# ESP32_with_USBC.net
KiCad netlist of a schematic drawn in Altium Designer
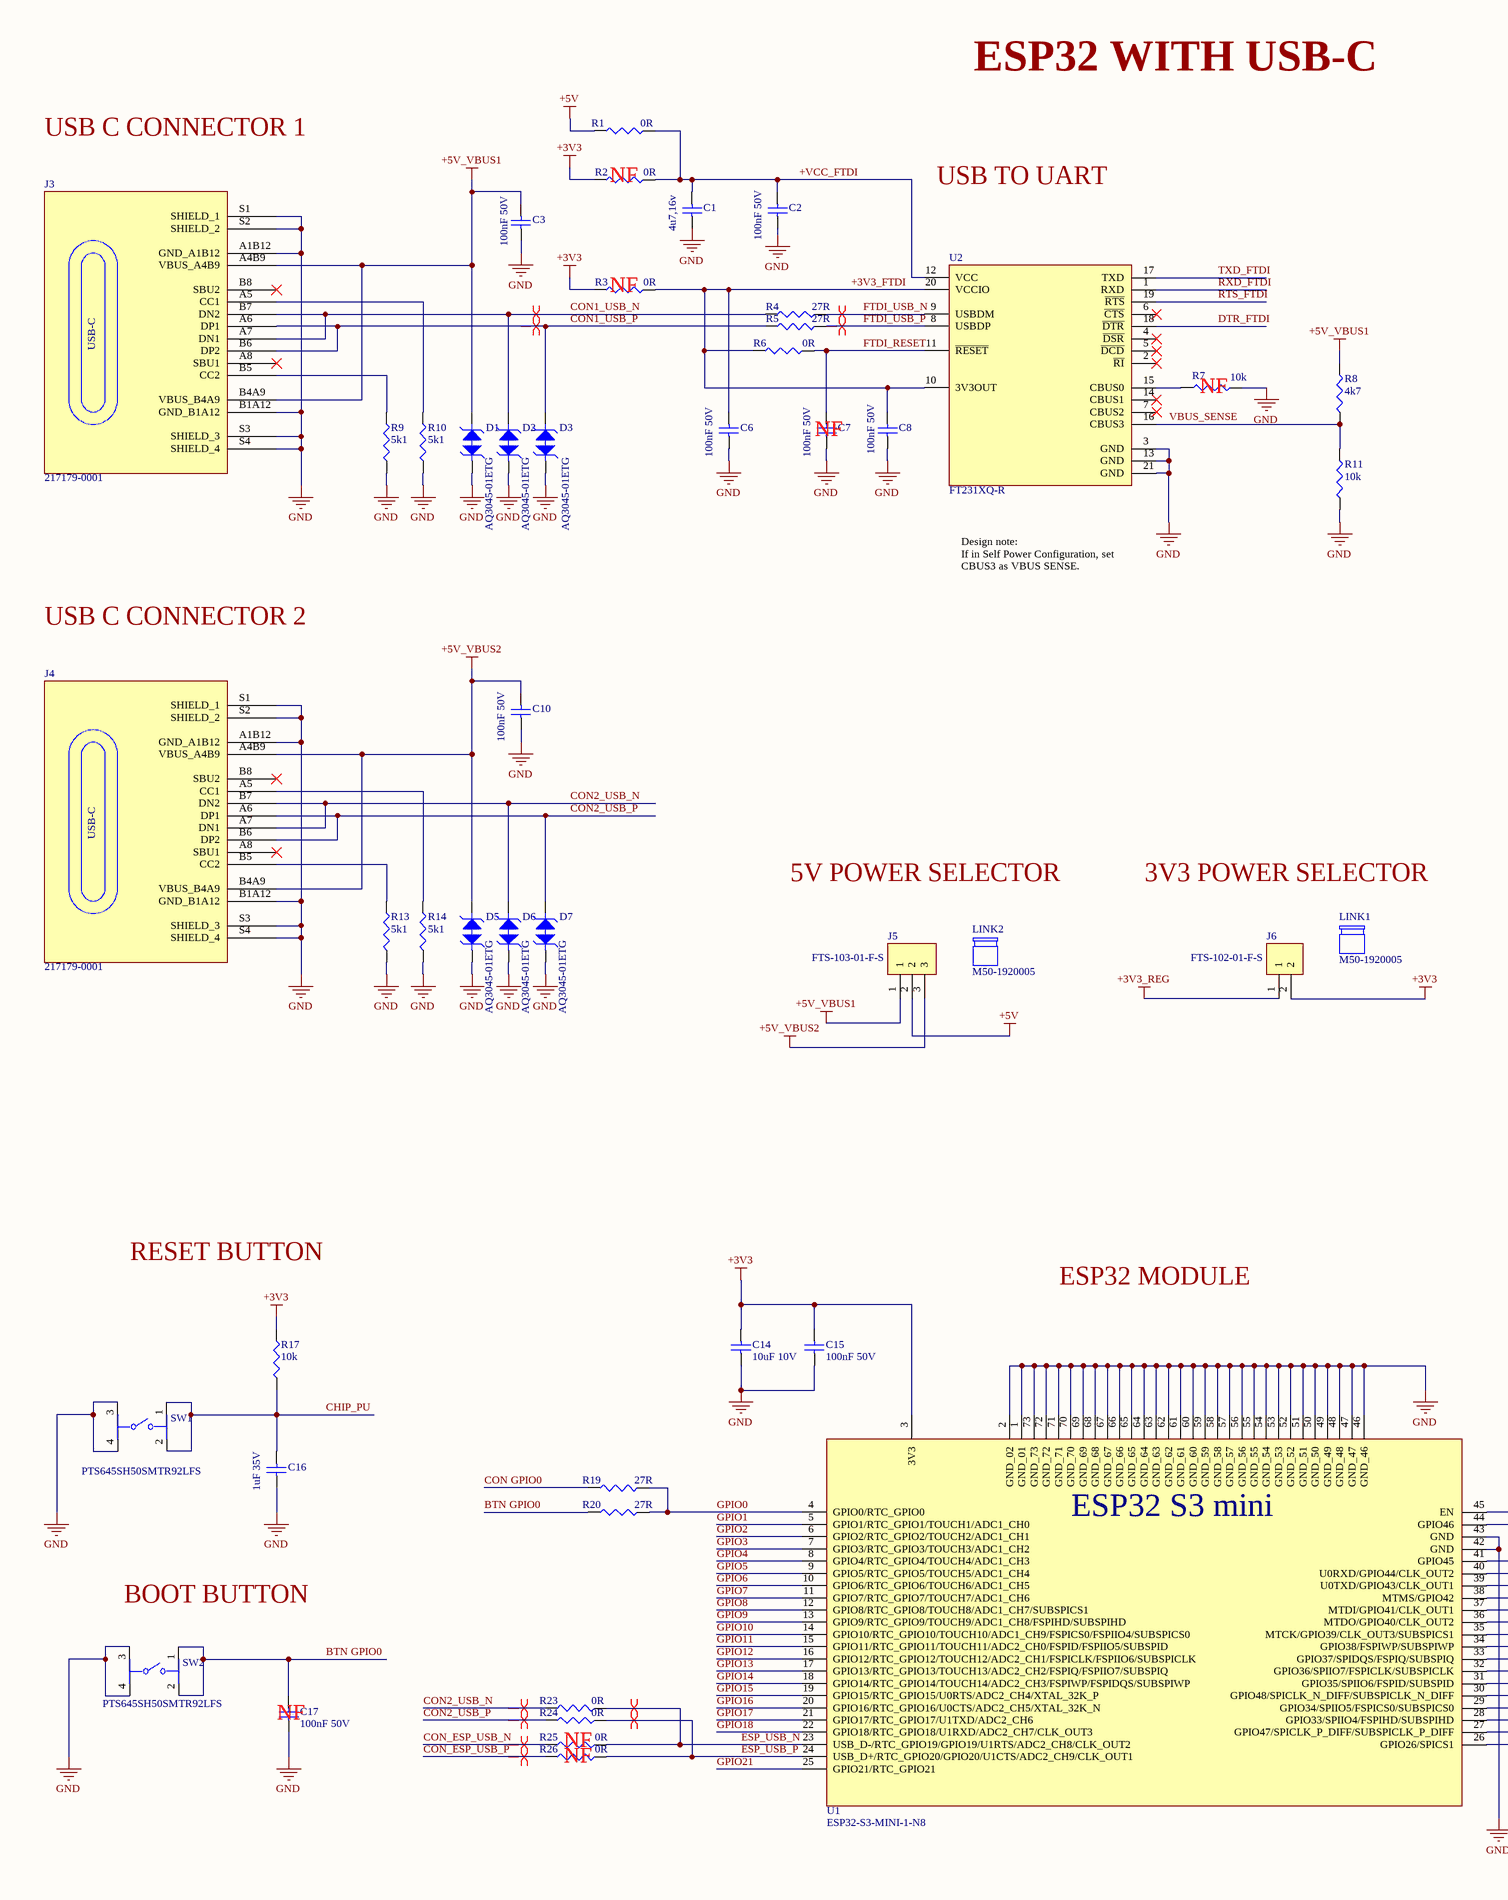
[diagram p0: ESP32 with USBC.SchDoc, left]
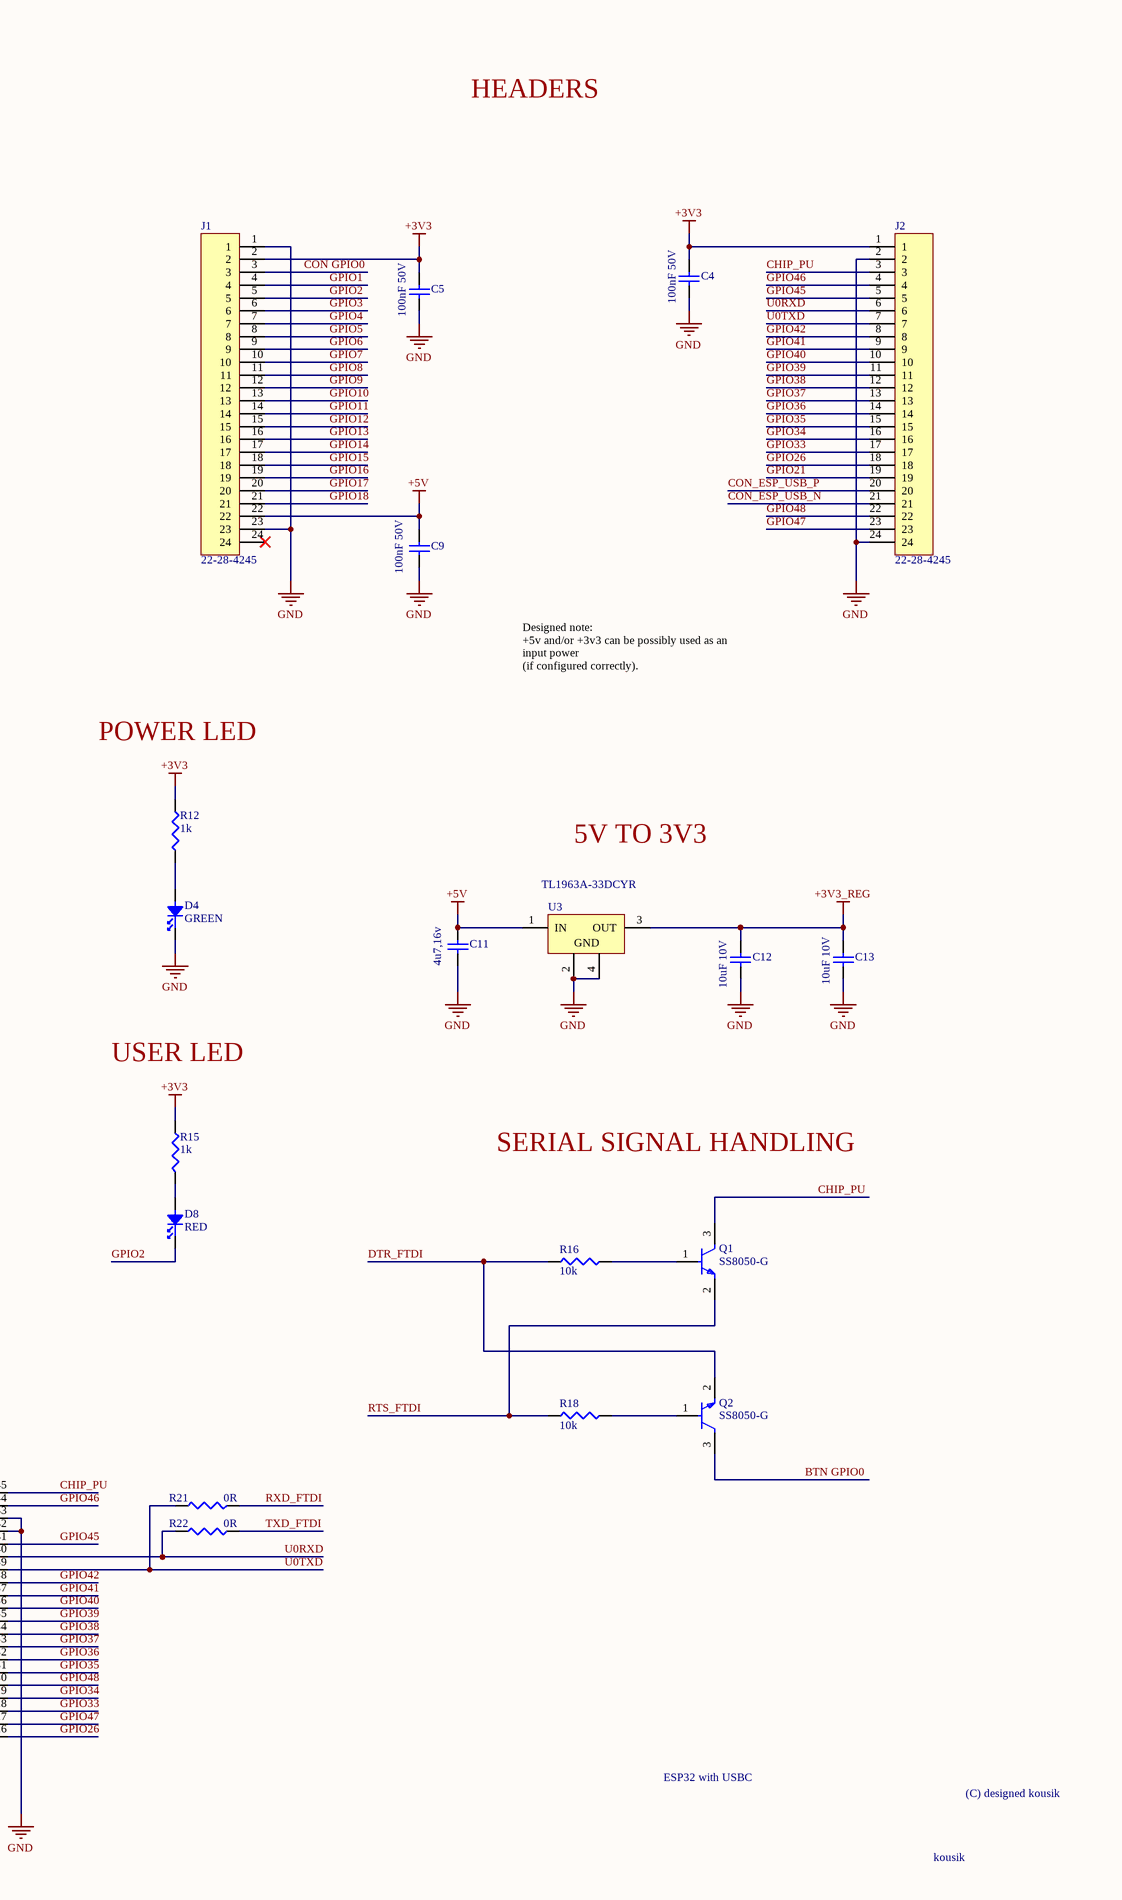
[diagram p1: ESP32 with USBC.SchDoc, right]

(export (version "E")
  (design (tool "Eeschema 10.0.6"))
  (components
    (comp (ref "C1")
      (value "4u7,16v")
      (footprint "CAPC1005X65N")
      (description "CAP CER 4.7UF 16V X5R 0402")
      (fields
        (field (name "MANUFACTURER") "Samsung Electro-Mechanics")
        (field (name "MANUFACTURER PART NUMBER") "CL05A475MO5NUNC")
      )
      (libsource (lib "Schlib") (part "CL05A475MO5NUNC"))
    )
    (comp (ref "C2")
      (value "100nF 50V")
      (footprint "CAPC1005X65N")
      (description "CAP CER 0.1UF 50V X7R 0402")
      (fields
        (field (name "MANUFACTURER") "Samsung Electro-Mechanics")
        (field (name "MANUFACTURER PART NUMBER") "CL05B104KB54PNC")
      )
      (libsource (lib "Schlib") (part "CL05B104KB54PNC"))
    )
    (comp (ref "C3")
      (value "100nF 50V")
      (footprint "CAPC1005X65N")
      (description "CAP CER 0.1UF 50V X7R 0402")
      (fields
        (field (name "MANUFACTURER") "Samsung Electro-Mechanics")
        (field (name "MANUFACTURER PART NUMBER") "CL05B104KB54PNC")
      )
      (libsource (lib "Schlib") (part "CL05B104KB54PNC"))
    )
    (comp (ref "C4")
      (value "100nF 50V")
      (footprint "CAPC1005X65N")
      (description "CAP CER 0.1UF 50V X7R 0402")
      (fields
        (field (name "MANUFACTURER") "Samsung Electro-Mechanics")
        (field (name "MANUFACTURER PART NUMBER") "CL05B104KB54PNC")
      )
      (libsource (lib "Schlib") (part "CL05B104KB54PNC"))
    )
    (comp (ref "C5")
      (value "100nF 50V")
      (footprint "CAPC1005X65N")
      (description "CAP CER 0.1UF 50V X7R 0402")
      (fields
        (field (name "MANUFACTURER") "Samsung Electro-Mechanics")
        (field (name "MANUFACTURER PART NUMBER") "CL05B104KB54PNC")
      )
      (libsource (lib "Schlib") (part "CL05B104KB54PNC"))
    )
    (comp (ref "C6")
      (value "100nF 50V")
      (footprint "CAPC1005X65N")
      (description "CAP CER 0.1UF 50V X7R 0402")
      (fields
        (field (name "MANUFACTURER") "Samsung Electro-Mechanics")
        (field (name "MANUFACTURER PART NUMBER") "CL05B104KB54PNC")
      )
      (libsource (lib "Schlib") (part "CL05B104KB54PNC"))
    )
    (comp (ref "C7")
      (value "100nF 50V")
      (footprint "CAPC1005X65N")
      (description "CAP CER 0.1UF 50V X7R 0402")
      (fields
        (field (name "MANUFACTURER") "Samsung Electro-Mechanics")
        (field (name "MANUFACTURER PART NUMBER") "CL05B104KB54PNC")
      )
      (libsource (lib "Schlib") (part "CL05B104KB54PNC"))
    )
    (comp (ref "C8")
      (value "100nF 50V")
      (footprint "CAPC1005X65N")
      (description "CAP CER 0.1UF 50V X7R 0402")
      (fields
        (field (name "MANUFACTURER") "Samsung Electro-Mechanics")
        (field (name "MANUFACTURER PART NUMBER") "CL05B104KB54PNC")
      )
      (libsource (lib "Schlib") (part "CL05B104KB54PNC"))
    )
    (comp (ref "C9")
      (value "100nF 50V")
      (footprint "CAPC1005X65N")
      (description "CAP CER 0.1UF 50V X7R 0402")
      (fields
        (field (name "MANUFACTURER") "Samsung Electro-Mechanics")
        (field (name "MANUFACTURER PART NUMBER") "CL05B104KB54PNC")
      )
      (libsource (lib "Schlib") (part "CL05B104KB54PNC"))
    )
    (comp (ref "C10")
      (value "100nF 50V")
      (footprint "CAPC1005X65N")
      (description "CAP CER 0.1UF 50V X7R 0402")
      (fields
        (field (name "MANUFACTURER") "Samsung Electro-Mechanics")
        (field (name "MANUFACTURER PART NUMBER") "CL05B104KB54PNC")
      )
      (libsource (lib "Schlib") (part "CL05B104KB54PNC"))
    )
    (comp (ref "C11")
      (value "4u7,16v")
      (footprint "CAPC1005X65N")
      (description "CAP CER 4.7UF 16V X5R 0402")
      (fields
        (field (name "MANUFACTURER") "Samsung Electro-Mechanics")
        (field (name "MANUFACTURER PART NUMBER") "CL05A475MO5NUNC")
      )
      (libsource (lib "Schlib") (part "CL05A475MO5NUNC"))
    )
    (comp (ref "C12")
      (value "10uF 10V")
      (footprint "CAPC1005X65N")
      (description "CAP CER 10UF 10V X5R 0402")
      (fields
        (field (name "MANUFACTURER") "Samsung Electro-Mechanics")
        (field (name "MANUFACTURER PART NUMBER") "CL05A106MP8NUB8")
      )
      (libsource (lib "Schlib") (part "CL05A106MP8NUB8"))
    )
    (comp (ref "C13")
      (value "10uF 10V")
      (footprint "CAPC1005X65N")
      (description "CAP CER 10UF 10V X5R 0402")
      (fields
        (field (name "MANUFACTURER") "Samsung Electro-Mechanics")
        (field (name "MANUFACTURER PART NUMBER") "CL05A106MP8NUB8")
      )
      (libsource (lib "Schlib") (part "CL05A106MP8NUB8"))
    )
    (comp (ref "C14")
      (value "10uF 10V")
      (footprint "CAPC1005X65N")
      (description "CAP CER 10UF 10V X5R 0402")
      (fields
        (field (name "MANUFACTURER") "Samsung Electro-Mechanics")
        (field (name "MANUFACTURER PART NUMBER") "CL05A106MP8NUB8")
      )
      (libsource (lib "Schlib") (part "CL05A106MP8NUB8"))
    )
    (comp (ref "C15")
      (value "100nF 50V")
      (footprint "CAPC1005X65N")
      (description "CAP CER 0.1UF 50V X7R 0402")
      (fields
        (field (name "MANUFACTURER") "Samsung Electro-Mechanics")
        (field (name "MANUFACTURER PART NUMBER") "CL05B104KB54PNC")
      )
      (libsource (lib "Schlib") (part "CL05B104KB54PNC"))
    )
    (comp (ref "C16")
      (value "1uF 35V")
      (footprint "CAPC1005X65N")
      (description "CAP CER 1UF 35V X5R 0402")
      (fields
        (field (name "MANUFACTURER") "Samsung Electro-Mechanics")
        (field (name "MANUFACTURER PART NUMBER") "CL05A105KL5NRNC")
      )
      (libsource (lib "Schlib") (part "CL05A105KL5NRNC"))
    )
    (comp (ref "C17")
      (value "100nF 50V")
      (footprint "CAPC1005X65N")
      (description "CAP CER 0.1UF 50V X7R 0402")
      (fields
        (field (name "MANUFACTURER") "Samsung Electro-Mechanics")
        (field (name "MANUFACTURER PART NUMBER") "CL05B104KB54PNC")
      )
      (libsource (lib "Schlib") (part "CL05B104KB54PNC"))
    )
    (comp (ref "D1")
      (value "AQ3045-01ETG")
      (footprint "SOD882")
      (description "TVS DIODE 5.3VWM 12VC SOD882")
      (fields (field (name "MANUFACTURER") "Littelfuse") (field (name "LCSC PART NUMBER") "C3710326"))
      (libsource (lib "Schlib") (part "AQ3045-01ETG"))
    )
    (comp (ref "D2")
      (value "AQ3045-01ETG")
      (footprint "SOD882")
      (description "TVS DIODE 5.3VWM 12VC SOD882")
      (fields (field (name "MANUFACTURER") "Littelfuse") (field (name "LCSC PART NUMBER") "C3710326"))
      (libsource (lib "Schlib") (part "AQ3045-01ETG"))
    )
    (comp (ref "D3")
      (value "AQ3045-01ETG")
      (footprint "SOD882")
      (description "TVS DIODE 5.3VWM 12VC SOD882")
      (fields (field (name "MANUFACTURER") "Littelfuse") (field (name "LCSC PART NUMBER") "C3710326"))
      (libsource (lib "Schlib") (part "AQ3045-01ETG"))
    )
    (comp (ref "D4")
      (value "GREEN")
      (footprint "LED0402G")
      (description "LED YLW-GRN 0402 SMD")
      (fields
        (field (name "MANUFACTURER") "Vishay")
        (field (name "MANUFACTURER PART NUMBER") "VLMG1500-GS08")
      )
      (libsource (lib "Schlib") (part "VLMG1500-GS08"))
    )
    (comp (ref "D5")
      (value "AQ3045-01ETG")
      (footprint "SOD882")
      (description "TVS DIODE 5.3VWM 12VC SOD882")
      (fields (field (name "MANUFACTURER") "Littelfuse") (field (name "LCSC PART NUMBER") "C3710326"))
      (libsource (lib "Schlib") (part "AQ3045-01ETG"))
    )
    (comp (ref "D6")
      (value "AQ3045-01ETG")
      (footprint "SOD882")
      (description "TVS DIODE 5.3VWM 12VC SOD882")
      (fields (field (name "MANUFACTURER") "Littelfuse") (field (name "LCSC PART NUMBER") "C3710326"))
      (libsource (lib "Schlib") (part "AQ3045-01ETG"))
    )
    (comp (ref "D7")
      (value "AQ3045-01ETG")
      (footprint "SOD882")
      (description "TVS DIODE 5.3VWM 12VC SOD882")
      (fields (field (name "MANUFACTURER") "Littelfuse") (field (name "LCSC PART NUMBER") "C3710326"))
      (libsource (lib "Schlib") (part "AQ3045-01ETG"))
    )
    (comp (ref "D8")
      (value "RED")
      (footprint "LED0402R")
      (description "LED RED 0402 SMD")
      (fields
        (field (name "MANUFACTURER") "Vishay")
        (field (name "MANUFACTURER PART NUMBER") "VLMS1500-GS08")
      )
      (libsource (lib "Schlib") (part "VLMS1500-GS08"))
    )
    (comp (ref "J1")
      (value "22-28-4245")
      (footprint "HDR_1X24_2.54MM")
      (description "CONN HEADER VERT 24POS 2.54MM")
      (fields (field (name "MANUFACTURER") "Molex") (field (name "LCSC PART NUMBER") "C7145888"))
      (libsource (lib "") (part "22-28-4245_1"))
    )
    (comp (ref "J2")
      (value "22-28-4245")
      (footprint "HDR_1X24_2.54MM")
      (description "CONN HEADER VERT 24POS 2.54MM")
      (fields (field (name "MANUFACTURER") "Molex") (field (name "LCSC PART NUMBER") "C7145888"))
      (libsource (lib "Schlib") (part "22-28-4245"))
    )
    (comp (ref "J3")
      (value "217179-0001")
      (footprint "FP-2171790001-MFG")
      (description "CONN RCP USB2.0 TYP C 24P SMD RA")
      (fields (field (name "MANUFACTURER") "Molex") (field (name "LCSC PART NUMBER") "C3197684"))
      (libsource (lib "Schlib") (part "217179-0001"))
    )
    (comp (ref "J4")
      (value "217179-0001")
      (footprint "FP-2171790001-MFG")
      (description "CONN RCP USB2.0 TYP C 24P SMD RA")
      (fields (field (name "MANUFACTURER") "Molex") (field (name "LCSC PART NUMBER") "C3197684"))
      (libsource (lib "Schlib") (part "217179-0001"))
    )
    (comp (ref "J5")
      (value "FTS-103-01-F-S")
      (footprint "HDR_1X3_1.27MM")
      (description "CONN HEADER VERT 3POS 1.27MM")
      (fields (field (name "MANUFACTURER") "Samtec") (field (name "LCSC PART NUMBER") "C3333578"))
      (libsource (lib "Schlib") (part "FTS-103-01-F-S"))
    )
    (comp (ref "J6")
      (value "FTS-102-01-F-S")
      (footprint "HDR_1X2_1.27MM")
      (description "CONN HEADER VERT 2POS 1.27MM")
      (fields (field (name "MANUFACTURER") "Samtec") (field (name "LCSC PART NUMBER") "C6045317"))
      (libsource (lib "Schlib") (part "FTS-102-01-F-S"))
    )
    (comp (ref "LINK1")
      (value "M50-1920005")
      (description "CONN SHUNT 1.27MM RED")
      (fields (field (name "MANUFACTURER") "Harwin") (field (name "LCSC PART NUMBER") "C6985646"))
      (libsource (lib "Schlib") (part "M50-1920005"))
    )
    (comp (ref "LINK2")
      (value "M50-1920005")
      (description "CONN SHUNT 1.27MM RED")
      (fields (field (name "MANUFACTURER") "Harwin") (field (name "LCSC PART NUMBER") "C6985646"))
      (libsource (lib "Schlib") (part "M50-1920005"))
    )
    (comp (ref "Q1")
      (value "SS8050-G")
      (footprint "FP-SS8050-G-IPC_B")
      (description "TRANS NPN 25V 1.5A SOT-23-3")
      (fields (field (name "MANUFACTURER") "Comchip") (field (name "LCSC PART NUMBER") "C164886"))
      (libsource (lib "Schlib") (part "SS8050-G"))
    )
    (comp (ref "Q2")
      (value "SS8050-G")
      (footprint "FP-SS8050-G-IPC_B")
      (description "TRANS NPN 25V 1.5A SOT-23-3")
      (fields (field (name "MANUFACTURER") "Comchip") (field (name "LCSC PART NUMBER") "C164886"))
      (libsource (lib "Schlib") (part "SS8050-G"))
    )
    (comp (ref "R1")
      (value "0R")
      (footprint "RESC1005X37N")
      (description "RES 0 OHM JUMPER 1/16W 0402")
      (fields
        (field (name "MANUFACTURER") "Yageo Group")
        (field (name "MANUFACTURER PART NUMBER") "RC0402JR-070RL")
      )
      (libsource (lib "Schlib") (part "RC0402JR-070RL"))
    )
    (comp (ref "R2")
      (value "0R")
      (footprint "RESC1005X37N")
      (description "RES 0 OHM JUMPER 1/16W 0402")
      (fields
        (field (name "MANUFACTURER") "Yageo Group")
        (field (name "MANUFACTURER PART NUMBER") "RC0402JR-070RL")
      )
      (libsource (lib "Schlib") (part "RC0402JR-070RL"))
    )
    (comp (ref "R3")
      (value "0R")
      (footprint "RESC1005X37N")
      (description "RES 0 OHM JUMPER 1/16W 0402")
      (fields
        (field (name "MANUFACTURER") "Yageo Group")
        (field (name "MANUFACTURER PART NUMBER") "RC0402JR-070RL")
      )
      (libsource (lib "Schlib") (part "RC0402JR-070RL"))
    )
    (comp (ref "R4")
      (value "27R")
      (footprint "RESC1005X37N")
      (description "RES 27 OHM 1% 1/16W 0402")
      (fields
        (field (name "MANUFACTURER") "Yageo Group")
        (field (name "MANUFACTURER PART NUMBER") "RC0402FR-0727RL")
      )
      (libsource (lib "Schlib") (part "RC0402FR-0727RL"))
    )
    (comp (ref "R5")
      (value "27R")
      (footprint "RESC1005X37N")
      (description "RES 27 OHM 1% 1/16W 0402")
      (fields
        (field (name "MANUFACTURER") "Yageo Group")
        (field (name "MANUFACTURER PART NUMBER") "RC0402FR-0727RL")
      )
      (libsource (lib "Schlib") (part "RC0402FR-0727RL"))
    )
    (comp (ref "R6")
      (value "0R")
      (footprint "RESC1005X37N")
      (description "RES 0 OHM JUMPER 1/16W 0402")
      (fields
        (field (name "MANUFACTURER") "Yageo Group")
        (field (name "MANUFACTURER PART NUMBER") "RC0402JR-070RL")
      )
      (libsource (lib "Schlib") (part "RC0402JR-070RL"))
    )
    (comp (ref "R7")
      (value "10k")
      (footprint "RESC1005X37N")
      (description "RES SMD 10K OHM 1% 1/16W 0402")
      (fields
        (field (name "MANUFACTURER") "Yageo Group")
        (field (name "MANUFACTURER PART NUMBER") "AC0402FR-0710KL")
      )
      (libsource (lib "Schlib") (part "AC0402FR-0710KL"))
    )
    (comp (ref "R8")
      (value "4k7")
      (footprint "RESC1005X37N")
      (description "RES 4.7K OHM 1% 1/16W 0402")
      (fields
        (field (name "MANUFACTURER") "Yageo Group")
        (field (name "MANUFACTURER PART NUMBER") "RC0402FR-074K7L")
      )
      (libsource (lib "Schlib") (part "RC0402FR-074K7L"))
    )
    (comp (ref "R9")
      (value "5k1")
      (footprint "RESC1005X37N")
      (description "RES SMD 5.1K OHM 1% 1/16W 0402")
      (fields
        (field (name "MANUFACTURER") "Yageo Group")
        (field (name "MANUFACTURER PART NUMBER") "AC0402FR-075K1L")
      )
      (libsource (lib "Schlib") (part "AC0402FR-075K1L"))
    )
    (comp (ref "R10")
      (value "5k1")
      (footprint "RESC1005X37N")
      (description "RES SMD 5.1K OHM 1% 1/16W 0402")
      (fields
        (field (name "MANUFACTURER") "Yageo Group")
        (field (name "MANUFACTURER PART NUMBER") "AC0402FR-075K1L")
      )
      (libsource (lib "Schlib") (part "AC0402FR-075K1L"))
    )
    (comp (ref "R11")
      (value "10k")
      (footprint "RESC1005X37N")
      (description "RES SMD 10K OHM 1% 1/16W 0402")
      (fields
        (field (name "MANUFACTURER") "Yageo Group")
        (field (name "MANUFACTURER PART NUMBER") "AC0402FR-0710KL")
      )
      (libsource (lib "Schlib") (part "AC0402FR-0710KL"))
    )
    (comp (ref "R12")
      (value "1k")
      (footprint "RESC1005X37N")
      (description "RES 1K OHM 1% 1/16W 0402")
      (fields
        (field (name "MANUFACTURER") "Yageo Group")
        (field (name "MANUFACTURER PART NUMBER") "RC0402FR-071KL")
      )
      (libsource (lib "Schlib") (part "RC0402FR-071KL"))
    )
    (comp (ref "R13")
      (value "5k1")
      (footprint "RESC1005X37N")
      (description "RES SMD 5.1K OHM 1% 1/16W 0402")
      (fields
        (field (name "MANUFACTURER") "Yageo Group")
        (field (name "MANUFACTURER PART NUMBER") "AC0402FR-075K1L")
      )
      (libsource (lib "Schlib") (part "AC0402FR-075K1L"))
    )
    (comp (ref "R14")
      (value "5k1")
      (footprint "RESC1005X37N")
      (description "RES SMD 5.1K OHM 1% 1/16W 0402")
      (fields
        (field (name "MANUFACTURER") "Yageo Group")
        (field (name "MANUFACTURER PART NUMBER") "AC0402FR-075K1L")
      )
      (libsource (lib "Schlib") (part "AC0402FR-075K1L"))
    )
    (comp (ref "R15")
      (value "1k")
      (footprint "RESC1005X37N")
      (description "RES 1K OHM 1% 1/16W 0402")
      (fields
        (field (name "MANUFACTURER") "Yageo Group")
        (field (name "MANUFACTURER PART NUMBER") "RC0402FR-071KL")
      )
      (libsource (lib "Schlib") (part "RC0402FR-071KL"))
    )
    (comp (ref "R16")
      (value "10k")
      (footprint "RESC1005X37N")
      (description "RES SMD 10K OHM 1% 1/16W 0402")
      (fields
        (field (name "MANUFACTURER") "Yageo Group")
        (field (name "MANUFACTURER PART NUMBER") "AC0402FR-0710KL")
      )
      (libsource (lib "Schlib") (part "AC0402FR-0710KL"))
    )
    (comp (ref "R17")
      (value "10k")
      (footprint "RESC1005X37N")
      (description "RES SMD 10K OHM 1% 1/16W 0402")
      (fields
        (field (name "MANUFACTURER") "Yageo Group")
        (field (name "MANUFACTURER PART NUMBER") "AC0402FR-0710KL")
      )
      (libsource (lib "Schlib") (part "AC0402FR-0710KL"))
    )
    (comp (ref "R18")
      (value "10k")
      (footprint "RESC1005X37N")
      (description "RES SMD 10K OHM 1% 1/16W 0402")
      (fields
        (field (name "MANUFACTURER") "Yageo Group")
        (field (name "MANUFACTURER PART NUMBER") "AC0402FR-0710KL")
      )
      (libsource (lib "Schlib") (part "AC0402FR-0710KL"))
    )
    (comp (ref "R19")
      (value "27R")
      (footprint "RESC1005X37N")
      (description "RES 27 OHM 1% 1/16W 0402")
      (fields
        (field (name "MANUFACTURER") "Yageo Group")
        (field (name "MANUFACTURER PART NUMBER") "RC0402FR-0727RL")
      )
      (libsource (lib "Schlib") (part "RC0402FR-0727RL"))
    )
    (comp (ref "R20")
      (value "27R")
      (footprint "RESC1005X37N")
      (description "RES 27 OHM 1% 1/16W 0402")
      (fields
        (field (name "MANUFACTURER") "Yageo Group")
        (field (name "MANUFACTURER PART NUMBER") "RC0402FR-0727RL")
      )
      (libsource (lib "Schlib") (part "RC0402FR-0727RL"))
    )
    (comp (ref "R21")
      (value "0R")
      (footprint "RESC1005X37N")
      (description "RES 0 OHM JUMPER 1/16W 0402")
      (fields
        (field (name "MANUFACTURER") "Yageo Group")
        (field (name "MANUFACTURER PART NUMBER") "RC0402JR-070RL")
      )
      (libsource (lib "Schlib") (part "RC0402JR-070RL"))
    )
    (comp (ref "R22")
      (value "0R")
      (footprint "RESC1005X37N")
      (description "RES 0 OHM JUMPER 1/16W 0402")
      (fields
        (field (name "MANUFACTURER") "Yageo Group")
        (field (name "MANUFACTURER PART NUMBER") "RC0402JR-070RL")
      )
      (libsource (lib "Schlib") (part "RC0402JR-070RL"))
    )
    (comp (ref "R23")
      (value "0R")
      (footprint "RESC1005X37N")
      (description "RES 0 OHM JUMPER 1/16W 0402")
      (fields
        (field (name "MANUFACTURER") "Yageo Group")
        (field (name "MANUFACTURER PART NUMBER") "RC0402JR-070RL")
      )
      (libsource (lib "Schlib") (part "RC0402JR-070RL"))
    )
    (comp (ref "R24")
      (value "0R")
      (footprint "RESC1005X37N")
      (description "RES 0 OHM JUMPER 1/16W 0402")
      (fields
        (field (name "MANUFACTURER") "Yageo Group")
        (field (name "MANUFACTURER PART NUMBER") "RC0402JR-070RL")
      )
      (libsource (lib "Schlib") (part "RC0402JR-070RL"))
    )
    (comp (ref "R25")
      (value "0R")
      (footprint "RESC1005X37N")
      (description "RES 0 OHM JUMPER 1/16W 0402")
      (fields
        (field (name "MANUFACTURER") "Yageo Group")
        (field (name "MANUFACTURER PART NUMBER") "RC0402JR-070RL")
      )
      (libsource (lib "Schlib") (part "RC0402JR-070RL"))
    )
    (comp (ref "R26")
      (value "0R")
      (footprint "RESC1005X37N")
      (description "RES 0 OHM JUMPER 1/16W 0402")
      (fields
        (field (name "MANUFACTURER") "Yageo Group")
        (field (name "MANUFACTURER PART NUMBER") "RC0402JR-070RL")
      )
      (libsource (lib "Schlib") (part "RC0402JR-070RL"))
    )
    (comp (ref "SW1")
      (value "PTS645SH50SMTR92LFS")
      (footprint "FP-PTS645SH50SMTR92LFS-MFG")
      (description "SWITCH TACTILE SPST-NO 0.05A 12V")
      (fields (field (name "MANUFACTURER") "C&K Components") (field (name "LCSC PART NUMBER") "C221869"))
      (libsource (lib "Schlib") (part "PTS645SH50SMTR92LFS"))
    )
    (comp (ref "SW2")
      (value "PTS645SH50SMTR92LFS")
      (footprint "FP-PTS645SH50SMTR92LFS-MFG")
      (description "SWITCH TACTILE SPST-NO 0.05A 12V")
      (fields (field (name "MANUFACTURER") "C&K Components") (field (name "LCSC PART NUMBER") "C221869"))
      (libsource (lib "Schlib") (part "PTS645SH50SMTR92LFS"))
    )
    (comp (ref "U1")
      (value "ESP32-S3-MINI-1-N8")
      (footprint "XCVR_ESP32-S3-MINI-1-N8")
      (description "20.5dBm ESP32-S3FN8 Chip 2.4GHz SMD WiFi Modules ROHS")
      (fields (field (name "MANUFACTURER") "Espressif Systems") (field (name "LCSC PART NUMBER") "C2913206"))
      (libsource (lib "Schlib") (part "ESP32-S3-MINI-1-N8"))
    )
    (comp (ref "U2")
      (value "FT231XQ-R")
      (footprint "FP-QFN-20-IPC_B")
      (description "IC USB SERIAL FULL UART 20QFN")
      (fields (field (name "MANUFACTURER") "FTDI") (field (name "LCSC PART NUMBER") "C132159"))
      (libsource (lib "Schlib") (part "FT231XQ-R"))
    )
    (comp (ref "U3")
      (value "TL1963A-33DCYR")
      (footprint "DCY0004A_N")
      (description "IC REG LIN 3.3V 1.5A SOT-223-4")
      (fields (field (name "MANUFACTURER") "Texas Instruments") (field (name "LCSC PART NUMBER") "C181262"))
      (libsource (lib "Schlib") (part "TL1963A-33DCYR"))
    )
  )
  (nets
    (net (code "1") (name "+3V3") (class "Default")
      (node (ref "C14") (pin "2") (pinfunction "2_2") (pintype "passive"))
      (node (ref "C15") (pin "2") (pinfunction "2_2") (pintype "passive"))
      (node (ref "C4") (pin "2") (pinfunction "2_2") (pintype "passive"))
      (node (ref "C5") (pin "2") (pinfunction "2_2") (pintype "passive"))
      (node (ref "J1") (pin "2") (pinfunction "2_2") (pintype "passive"))
      (node (ref "J2") (pin "1") (pinfunction "1_1") (pintype "passive"))
      (node (ref "J6") (pin "2") (pinfunction "2_2") (pintype "passive"))
      (node (ref "R12") (pin "2") (pinfunction "2_2") (pintype "passive"))
      (node (ref "R15") (pin "2") (pinfunction "2_2") (pintype "passive"))
      (node (ref "R17") (pin "2") (pinfunction "2_2") (pintype "passive"))
      (node (ref "R2") (pin "1") (pinfunction "1_1") (pintype "passive"))
      (node (ref "R3") (pin "1") (pinfunction "1_1") (pintype "passive"))
      (node (ref "U1") (pin "3") (pinfunction "3V3_3") (pintype "passive"))
    )
    (net (code "2") (name "+3V3_REG") (class "Default")
      (node (ref "C12") (pin "2") (pinfunction "2_2") (pintype "passive"))
      (node (ref "C13") (pin "2") (pinfunction "2_2") (pintype "passive"))
      (node (ref "J6") (pin "1") (pinfunction "1_1") (pintype "passive"))
      (node (ref "U3") (pin "3") (pinfunction "OUT_3") (pintype "power_in"))
    )
    (net (code "3") (name "+5V") (class "Default")
      (node (ref "C11") (pin "2") (pinfunction "2_2") (pintype "passive"))
      (node (ref "C9") (pin "2") (pinfunction "2_2") (pintype "passive"))
      (node (ref "J1") (pin "22") (pinfunction "22_22") (pintype "passive"))
      (node (ref "J5") (pin "2") (pinfunction "2_2") (pintype "passive"))
      (node (ref "R1") (pin "1") (pinfunction "1_1") (pintype "passive"))
      (node (ref "U3") (pin "1") (pinfunction "IN_1") (pintype "power_in"))
    )
    (net (code "4") (name "+5V_VBUS1") (class "Default")
      (node (ref "C3") (pin "2") (pinfunction "2_2") (pintype "passive"))
      (node (ref "D1") (pin "2") (pinfunction "2_2") (pintype "passive"))
      (node (ref "J3") (pin "A4B9") (pinfunction "VBUS_A4B9_A4B9") (pintype "passive"))
      (node (ref "J3") (pin "B4A9") (pinfunction "VBUS_B4A9_B4A9") (pintype "passive"))
      (node (ref "J5") (pin "1") (pinfunction "1_1") (pintype "passive"))
      (node (ref "R8") (pin "2") (pinfunction "2_2") (pintype "passive"))
    )
    (net (code "5") (name "+5V_VBUS2") (class "Default")
      (node (ref "C10") (pin "2") (pinfunction "2_2") (pintype "passive"))
      (node (ref "D5") (pin "2") (pinfunction "2_2") (pintype "passive"))
      (node (ref "J4") (pin "A4B9") (pinfunction "VBUS_A4B9_A4B9") (pintype "passive"))
      (node (ref "J4") (pin "B4A9") (pinfunction "VBUS_B4A9_B4A9") (pintype "passive"))
      (node (ref "J5") (pin "3") (pinfunction "3_3") (pintype "passive"))
    )
    (net (code "6") (name "/+3V3_FTDI") (class "Default")
      (node (ref "C6") (pin "2") (pinfunction "2_2") (pintype "passive"))
      (node (ref "C8") (pin "2") (pinfunction "2_2") (pintype "passive"))
      (node (ref "R3") (pin "2") (pinfunction "2_2") (pintype "passive"))
      (node (ref "R6") (pin "1") (pinfunction "1_1") (pintype "passive"))
      (node (ref "U2") (pin "10") (pinfunction "3V3OUT_10") (pintype "passive"))
      (node (ref "U2") (pin "20") (pinfunction "VCCIO_20") (pintype "passive"))
    )
    (net (code "7") (name "/+VCC_FTDI") (class "Default")
      (node (ref "C1") (pin "2") (pinfunction "2_2") (pintype "passive"))
      (node (ref "C2") (pin "2") (pinfunction "2_2") (pintype "passive"))
      (node (ref "R1") (pin "2") (pinfunction "2_2") (pintype "passive"))
      (node (ref "R2") (pin "2") (pinfunction "2_2") (pintype "passive"))
      (node (ref "U2") (pin "12") (pinfunction "VCC_12") (pintype "passive"))
    )
    (net (code "8") (name "/BTN GPIO0") (class "Default")
      (node (ref "C17") (pin "2") (pinfunction "2_2") (pintype "passive"))
      (node (ref "Q2") (pin "3") (pinfunction "C_3") (pintype "passive"))
      (node (ref "R20") (pin "1") (pinfunction "1_1") (pintype "passive"))
      (node (ref "SW2") (pin "1") (pinfunction "1_1") (pintype "passive"))
      (node (ref "SW2") (pin "2") (pinfunction "2_2") (pintype "passive"))
    )
    (net (code "9") (name "/CHIP_PU") (class "Default")
      (node (ref "C16") (pin "2") (pinfunction "2_2") (pintype "passive"))
      (node (ref "J2") (pin "3") (pinfunction "3_3") (pintype "passive"))
      (node (ref "Q1") (pin "3") (pinfunction "C_3") (pintype "passive"))
      (node (ref "R17") (pin "1") (pinfunction "1_1") (pintype "passive"))
      (node (ref "SW1") (pin "1") (pinfunction "1_1") (pintype "passive"))
      (node (ref "SW1") (pin "2") (pinfunction "2_2") (pintype "passive"))
      (node (ref "U1") (pin "45") (pinfunction "EN_45") (pintype "passive"))
    )
    (net (code "10") (name "/CON GPIO0") (class "Default")
      (node (ref "J1") (pin "3") (pinfunction "3_3") (pintype "passive"))
      (node (ref "R19") (pin "1") (pinfunction "1_1") (pintype "passive"))
    )
    (net (code "11") (name "/CON1_USB_N") (class "Default")
      (node (ref "D2") (pin "2") (pinfunction "2_2") (pintype "passive"))
      (node (ref "J3") (pin "A7") (pinfunction "DN1_A7") (pintype "passive"))
      (node (ref "J3") (pin "B7") (pinfunction "DN2_B7") (pintype "passive"))
      (node (ref "R4") (pin "1") (pinfunction "1_1") (pintype "passive"))
    )
    (net (code "12") (name "/CON1_USB_P") (class "Default")
      (node (ref "D3") (pin "2") (pinfunction "2_2") (pintype "passive"))
      (node (ref "J3") (pin "A6") (pinfunction "DP1_A6") (pintype "passive"))
      (node (ref "J3") (pin "B6") (pinfunction "DP2_B6") (pintype "passive"))
      (node (ref "R5") (pin "1") (pinfunction "1_1") (pintype "passive"))
    )
    (net (code "13") (name "/CON2_USB_N") (class "Default")
      (node (ref "D6") (pin "2") (pinfunction "2_2") (pintype "passive"))
      (node (ref "J4") (pin "A7") (pinfunction "DN1_A7") (pintype "passive"))
      (node (ref "J4") (pin "B7") (pinfunction "DN2_B7") (pintype "passive"))
      (node (ref "R23") (pin "1") (pinfunction "1_1") (pintype "passive"))
    )
    (net (code "14") (name "/CON2_USB_P") (class "Default")
      (node (ref "D7") (pin "2") (pinfunction "2_2") (pintype "passive"))
      (node (ref "J4") (pin "A6") (pinfunction "DP1_A6") (pintype "passive"))
      (node (ref "J4") (pin "B6") (pinfunction "DP2_B6") (pintype "passive"))
      (node (ref "R24") (pin "1") (pinfunction "1_1") (pintype "passive"))
    )
    (net (code "15") (name "/CON_ESP_USB_N") (class "Default")
      (node (ref "J2") (pin "21") (pinfunction "21_21") (pintype "passive"))
      (node (ref "R25") (pin "1") (pinfunction "1_1") (pintype "passive"))
    )
    (net (code "16") (name "/CON_ESP_USB_P") (class "Default")
      (node (ref "J2") (pin "20") (pinfunction "20_20") (pintype "passive"))
      (node (ref "R26") (pin "1") (pinfunction "1_1") (pintype "passive"))
    )
    (net (code "17") (name "/DTR_FTDI") (class "Default")
      (node (ref "Q2") (pin "2") (pinfunction "E_2") (pintype "passive"))
      (node (ref "R16") (pin "2") (pinfunction "2_2") (pintype "passive"))
      (node (ref "U2") (pin "18") (pinfunction "~{DTR}_18") (pintype "passive"))
    )
    (net (code "18") (name "/ESP_USB_N") (class "Default")
      (node (ref "R23") (pin "2") (pinfunction "2_2") (pintype "passive"))
      (node (ref "R25") (pin "2") (pinfunction "2_2") (pintype "passive"))
      (node (ref "U1") (pin "23") (pinfunction "USB_D-/RTC_GPIO19/GPIO19/U1RTS/ADC2_CH8/CLK_OUT2_23") (pintype "passive"))
    )
    (net (code "19") (name "/ESP_USB_P") (class "Default")
      (node (ref "R24") (pin "2") (pinfunction "2_2") (pintype "passive"))
      (node (ref "R26") (pin "2") (pinfunction "2_2") (pintype "passive"))
      (node (ref "U1") (pin "24") (pinfunction "USB_D+/RTC_GPIO20/GPIO20/U1CTS/ADC2_CH9/CLK_OUT1_24") (pintype "passive"))
    )
    (net (code "20") (name "/FTDI_RESET") (class "Default")
      (node (ref "C7") (pin "2") (pinfunction "2_2") (pintype "passive"))
      (node (ref "R6") (pin "2") (pinfunction "2_2") (pintype "passive"))
      (node (ref "U2") (pin "11") (pinfunction "~{RESET}_11") (pintype "passive"))
    )
    (net (code "21") (name "/FTDI_USB_N") (class "Default")
      (node (ref "R4") (pin "2") (pinfunction "2_2") (pintype "passive"))
      (node (ref "U2") (pin "9") (pinfunction "USBDM_9") (pintype "passive"))
    )
    (net (code "22") (name "/FTDI_USB_P") (class "Default")
      (node (ref "R5") (pin "2") (pinfunction "2_2") (pintype "passive"))
      (node (ref "U2") (pin "8") (pinfunction "USBDP_8") (pintype "passive"))
    )
    (net (code "23") (name "/GPIO0") (class "Default")
      (node (ref "R19") (pin "2") (pinfunction "2_2") (pintype "passive"))
      (node (ref "R20") (pin "2") (pinfunction "2_2") (pintype "passive"))
      (node (ref "U1") (pin "4") (pinfunction "GPIO0/RTC_GPIO0_4") (pintype "passive"))
    )
    (net (code "24") (name "/GPIO1") (class "Default")
      (node (ref "J1") (pin "4") (pinfunction "4_4") (pintype "passive"))
      (node (ref "U1") (pin "5") (pinfunction "GPIO1/RTC_GPIO1/TOUCH1/ADC1_CH0_5") (pintype "passive"))
    )
    (net (code "25") (name "/GPIO2") (class "Default")
      (node (ref "D8") (pin "1") (pinfunction "1_1") (pintype "passive"))
      (node (ref "J1") (pin "5") (pinfunction "5_5") (pintype "passive"))
      (node (ref "U1") (pin "6") (pinfunction "GPIO2/RTC_GPIO2/TOUCH2/ADC1_CH1_6") (pintype "passive"))
    )
    (net (code "26") (name "/GPIO3") (class "Default")
      (node (ref "J1") (pin "6") (pinfunction "6_6") (pintype "passive"))
      (node (ref "U1") (pin "7") (pinfunction "GPIO3/RTC_GPIO3/TOUCH3/ADC1_CH2_7") (pintype "passive"))
    )
    (net (code "27") (name "/GPIO4") (class "Default")
      (node (ref "J1") (pin "7") (pinfunction "7_7") (pintype "passive"))
      (node (ref "U1") (pin "8") (pinfunction "GPIO4/RTC_GPIO4/TOUCH4/ADC1_CH3_8") (pintype "passive"))
    )
    (net (code "28") (name "/GPIO5") (class "Default")
      (node (ref "J1") (pin "8") (pinfunction "8_8") (pintype "passive"))
      (node (ref "U1") (pin "9") (pinfunction "GPIO5/RTC_GPIO5/TOUCH5/ADC1_CH4_9") (pintype "passive"))
    )
    (net (code "29") (name "/GPIO6") (class "Default")
      (node (ref "J1") (pin "9") (pinfunction "9_9") (pintype "passive"))
      (node (ref "U1") (pin "10") (pinfunction "GPIO6/RTC_GPIO6/TOUCH6/ADC1_CH5_10") (pintype "passive"))
    )
    (net (code "30") (name "/GPIO7") (class "Default")
      (node (ref "J1") (pin "10") (pinfunction "10_10") (pintype "passive"))
      (node (ref "U1") (pin "11") (pinfunction "GPIO7/RTC_GPIO7/TOUCH7/ADC1_CH6_11") (pintype "passive"))
    )
    (net (code "31") (name "/GPIO8") (class "Default")
      (node (ref "J1") (pin "11") (pinfunction "11_11") (pintype "passive"))
      (node (ref "U1") (pin "12") (pinfunction "GPIO8/RTC_GPIO8/TOUCH8/ADC1_CH7/SUBSPICS1_12") (pintype "passive"))
    )
    (net (code "32") (name "/GPIO9") (class "Default")
      (node (ref "J1") (pin "12") (pinfunction "12_12") (pintype "passive"))
      (node (ref "U1") (pin "13") (pinfunction "GPIO9/RTC_GPIO9/TOUCH9/ADC1_CH8/FSPIHD/SUBSPIHD_13") (pintype "passive"))
    )
    (net (code "33") (name "/GPIO10") (class "Default")
      (node (ref "J1") (pin "13") (pinfunction "13_13") (pintype "passive"))
      (node (ref "U1") (pin "14") (pinfunction "GPIO10/RTC_GPIO10/TOUCH10/ADC1_CH9/FSPICS0/FSPIIO4/SUBSPICS0_14") (pintype "passive"))
    )
    (net (code "34") (name "/GPIO11") (class "Default")
      (node (ref "J1") (pin "14") (pinfunction "14_14") (pintype "passive"))
      (node (ref "U1") (pin "15") (pinfunction "GPIO11/RTC_GPIO11/TOUCH11/ADC2_CH0/FSPID/FSPIIO5/SUBSPID_15") (pintype "passive"))
    )
    (net (code "35") (name "/GPIO12") (class "Default")
      (node (ref "J1") (pin "15") (pinfunction "15_15") (pintype "passive"))
      (node (ref "U1") (pin "16") (pinfunction "GPIO12/RTC_GPIO12/TOUCH12/ADC2_CH1/FSPICLK/FSPIIO6/SUBSPICLK_16") (pintype "passive"))
    )
    (net (code "36") (name "/GPIO13") (class "Default")
      (node (ref "J1") (pin "16") (pinfunction "16_16") (pintype "passive"))
      (node (ref "U1") (pin "17") (pinfunction "GPIO13/RTC_GPIO13/TOUCH13/ADC2_CH2/FSPIQ/FSPIIO7/SUBSPIQ_17") (pintype "passive"))
    )
    (net (code "37") (name "/GPIO14") (class "Default")
      (node (ref "J1") (pin "17") (pinfunction "17_17") (pintype "passive"))
      (node (ref "U1") (pin "18") (pinfunction "GPIO14/RTC_GPIO14/TOUCH14/ADC2_CH3/FSPIWP/FSPIDQS/SUBSPIWP_18") (pintype "passive"))
    )
    (net (code "38") (name "/GPIO15") (class "Default")
      (node (ref "J1") (pin "18") (pinfunction "18_18") (pintype "passive"))
      (node (ref "U1") (pin "19") (pinfunction "GPIO15/RTC_GPIO15/U0RTS/ADC2_CH4/XTAL_32K_P_19") (pintype "passive"))
    )
    (net (code "39") (name "/GPIO16") (class "Default")
      (node (ref "J1") (pin "19") (pinfunction "19_19") (pintype "passive"))
      (node (ref "U1") (pin "20") (pinfunction "GPIO16/RTC_GPIO16/U0CTS/ADC2_CH5/XTAL_32K_N_20") (pintype "passive"))
    )
    (net (code "40") (name "/GPIO17") (class "Default")
      (node (ref "J1") (pin "20") (pinfunction "20_20") (pintype "passive"))
      (node (ref "U1") (pin "21") (pinfunction "GPIO17/RTC_GPIO17/U1TXD/ADC2_CH6_21") (pintype "passive"))
    )
    (net (code "41") (name "/GPIO18") (class "Default")
      (node (ref "J1") (pin "21") (pinfunction "21_21") (pintype "passive"))
      (node (ref "U1") (pin "22") (pinfunction "GPIO18/RTC_GPIO18/U1RXD/ADC2_CH7/CLK_OUT3_22") (pintype "passive"))
    )
    (net (code "42") (name "/GPIO21") (class "Default")
      (node (ref "J2") (pin "19") (pinfunction "19_19") (pintype "passive"))
      (node (ref "U1") (pin "25") (pinfunction "GPIO21/RTC_GPIO21_25") (pintype "passive"))
    )
    (net (code "43") (name "/GPIO26") (class "Default")
      (node (ref "J2") (pin "18") (pinfunction "18_18") (pintype "passive"))
      (node (ref "U1") (pin "26") (pinfunction "GPIO26/SPICS1_26") (pintype "passive"))
    )
    (net (code "44") (name "/GPIO33") (class "Default")
      (node (ref "J2") (pin "17") (pinfunction "17_17") (pintype "passive"))
      (node (ref "U1") (pin "28") (pinfunction "GPIO33/SPIIO4/FSPIHD/SUBSPIHD_28") (pintype "passive"))
    )
    (net (code "45") (name "/GPIO34") (class "Default")
      (node (ref "J2") (pin "16") (pinfunction "16_16") (pintype "passive"))
      (node (ref "U1") (pin "29") (pinfunction "GPIO34/SPIIO5/FSPICS0/SUBSPICS0_29") (pintype "passive"))
    )
    (net (code "46") (name "/GPIO35") (class "Default")
      (node (ref "J2") (pin "15") (pinfunction "15_15") (pintype "passive"))
      (node (ref "U1") (pin "31") (pinfunction "GPIO35/SPIIO6/FSPID/SUBSPID_31") (pintype "passive"))
    )
    (net (code "47") (name "/GPIO36") (class "Default")
      (node (ref "J2") (pin "14") (pinfunction "14_14") (pintype "passive"))
      (node (ref "U1") (pin "32") (pinfunction "GPIO36/SPIIO7/FSPICLK/SUBSPICLK_32") (pintype "passive"))
    )
    (net (code "48") (name "/GPIO37") (class "Default")
      (node (ref "J2") (pin "13") (pinfunction "13_13") (pintype "passive"))
      (node (ref "U1") (pin "33") (pinfunction "GPIO37/SPIDQS/FSPIQ/SUBSPIQ_33") (pintype "passive"))
    )
    (net (code "49") (name "/GPIO38") (class "Default")
      (node (ref "J2") (pin "12") (pinfunction "12_12") (pintype "passive"))
      (node (ref "U1") (pin "34") (pinfunction "GPIO38/FSPIWP/SUBSPIWP_34") (pintype "passive"))
    )
    (net (code "50") (name "/GPIO39") (class "Default")
      (node (ref "J2") (pin "11") (pinfunction "11_11") (pintype "passive"))
      (node (ref "U1") (pin "35") (pinfunction "MTCK/GPIO39/CLK_OUT3/SUBSPICS1_35") (pintype "passive"))
    )
    (net (code "51") (name "/GPIO40") (class "Default")
      (node (ref "J2") (pin "10") (pinfunction "10_10") (pintype "passive"))
      (node (ref "U1") (pin "36") (pinfunction "MTDO/GPIO40/CLK_OUT2_36") (pintype "passive"))
    )
    (net (code "52") (name "/GPIO41") (class "Default")
      (node (ref "J2") (pin "9") (pinfunction "9_9") (pintype "passive"))
      (node (ref "U1") (pin "37") (pinfunction "MTDI/GPIO41/CLK_OUT1_37") (pintype "passive"))
    )
    (net (code "53") (name "/GPIO42") (class "Default")
      (node (ref "J2") (pin "8") (pinfunction "8_8") (pintype "passive"))
      (node (ref "U1") (pin "38") (pinfunction "MTMS/GPIO42_38") (pintype "passive"))
    )
    (net (code "54") (name "/GPIO45") (class "Default")
      (node (ref "J2") (pin "5") (pinfunction "5_5") (pintype "passive"))
      (node (ref "U1") (pin "41") (pinfunction "GPIO45_41") (pintype "passive"))
    )
    (net (code "55") (name "/GPIO46") (class "Default")
      (node (ref "J2") (pin "4") (pinfunction "4_4") (pintype "passive"))
      (node (ref "U1") (pin "44") (pinfunction "GPIO46_44") (pintype "passive"))
    )
    (net (code "56") (name "/GPIO47") (class "Default")
      (node (ref "J2") (pin "23") (pinfunction "23_23") (pintype "passive"))
      (node (ref "U1") (pin "27") (pinfunction "GPIO47/SPICLK_P_DIFF/SUBSPICLK_P_DIFF_27") (pintype "passive"))
    )
    (net (code "57") (name "/GPIO48") (class "Default")
      (node (ref "J2") (pin "22") (pinfunction "22_22") (pintype "passive"))
      (node (ref "U1") (pin "30") (pinfunction "GPIO48/SPICLK_N_DIFF/SUBSPICLK_N_DIFF_30") (pintype "passive"))
    )
    (net (code "58") (name "/RTS_FTDI") (class "Default")
      (node (ref "Q1") (pin "2") (pinfunction "E_2") (pintype "passive"))
      (node (ref "R18") (pin "2") (pinfunction "2_2") (pintype "passive"))
      (node (ref "U2") (pin "19") (pinfunction "~{RTS}_19") (pintype "passive"))
    )
    (net (code "59") (name "/RXD_FTDI") (class "Default")
      (node (ref "R21") (pin "2") (pinfunction "2_2") (pintype "passive"))
      (node (ref "U2") (pin "1") (pinfunction "RXD_1") (pintype "passive"))
    )
    (net (code "60") (name "/TXD_FTDI") (class "Default")
      (node (ref "R22") (pin "2") (pinfunction "2_2") (pintype "passive"))
      (node (ref "U2") (pin "17") (pinfunction "TXD_17") (pintype "passive"))
    )
    (net (code "61") (name "/U0RXD") (class "Default")
      (node (ref "J2") (pin "6") (pinfunction "6_6") (pintype "passive"))
      (node (ref "R22") (pin "1") (pinfunction "1_1") (pintype "passive"))
      (node (ref "U1") (pin "40") (pinfunction "U0RXD/GPIO44/CLK_OUT2_40") (pintype "passive"))
    )
    (net (code "62") (name "/U0TXD") (class "Default")
      (node (ref "J2") (pin "7") (pinfunction "7_7") (pintype "passive"))
      (node (ref "R21") (pin "1") (pinfunction "1_1") (pintype "passive"))
      (node (ref "U1") (pin "39") (pinfunction "U0TXD/GPIO43/CLK_OUT1_39") (pintype "passive"))
    )
    (net (code "63") (name "/VBUS_SENSE") (class "Default")
      (node (ref "R11") (pin "2") (pinfunction "2_2") (pintype "passive"))
      (node (ref "R8") (pin "1") (pinfunction "1_1") (pintype "passive"))
      (node (ref "U2") (pin "16") (pinfunction "CBUS3_16") (pintype "passive"))
    )
    (net (code "64") (name "GND") (class "Default")
      (node (ref "C1") (pin "1") (pinfunction "1_1") (pintype "passive"))
      (node (ref "C10") (pin "1") (pinfunction "1_1") (pintype "passive"))
      (node (ref "C11") (pin "1") (pinfunction "1_1") (pintype "passive"))
      (node (ref "C12") (pin "1") (pinfunction "1_1") (pintype "passive"))
      (node (ref "C13") (pin "1") (pinfunction "1_1") (pintype "passive"))
      (node (ref "C14") (pin "1") (pinfunction "1_1") (pintype "passive"))
      (node (ref "C15") (pin "1") (pinfunction "1_1") (pintype "passive"))
      (node (ref "C16") (pin "1") (pinfunction "1_1") (pintype "passive"))
      (node (ref "C17") (pin "1") (pinfunction "1_1") (pintype "passive"))
      (node (ref "C2") (pin "1") (pinfunction "1_1") (pintype "passive"))
      (node (ref "C3") (pin "1") (pinfunction "1_1") (pintype "passive"))
      (node (ref "C4") (pin "1") (pinfunction "1_1") (pintype "passive"))
      (node (ref "C5") (pin "1") (pinfunction "1_1") (pintype "passive"))
      (node (ref "C6") (pin "1") (pinfunction "1_1") (pintype "passive"))
      (node (ref "C7") (pin "1") (pinfunction "1_1") (pintype "passive"))
      (node (ref "C8") (pin "1") (pinfunction "1_1") (pintype "passive"))
      (node (ref "C9") (pin "1") (pinfunction "1_1") (pintype "passive"))
      (node (ref "D1") (pin "1") (pinfunction "1_1") (pintype "passive"))
      (node (ref "D2") (pin "1") (pinfunction "1_1") (pintype "passive"))
      (node (ref "D3") (pin "1") (pinfunction "1_1") (pintype "passive"))
      (node (ref "D4") (pin "1") (pinfunction "1_1") (pintype "passive"))
      (node (ref "D5") (pin "1") (pinfunction "1_1") (pintype "passive"))
      (node (ref "D6") (pin "1") (pinfunction "1_1") (pintype "passive"))
      (node (ref "D7") (pin "1") (pinfunction "1_1") (pintype "passive"))
      (node (ref "J1") (pin "1") (pinfunction "1_1") (pintype "passive"))
      (node (ref "J1") (pin "23") (pinfunction "23_23") (pintype "passive"))
      (node (ref "J2") (pin "2") (pinfunction "2_2") (pintype "passive"))
      (node (ref "J2") (pin "24") (pinfunction "24_24") (pintype "passive"))
      (node (ref "J3") (pin "A1B12") (pinfunction "GND_A1B12_A1B12") (pintype "passive"))
      (node (ref "J3") (pin "B1A12") (pinfunction "GND_B1A12_B1A12") (pintype "passive"))
      (node (ref "J3") (pin "S1") (pinfunction "SHIELD_1_S1") (pintype "passive"))
      (node (ref "J3") (pin "S2") (pinfunction "SHIELD_2_S2") (pintype "passive"))
      (node (ref "J3") (pin "S3") (pinfunction "SHIELD_3_S3") (pintype "passive"))
      (node (ref "J3") (pin "S4") (pinfunction "SHIELD_4_S4") (pintype "passive"))
      (node (ref "J4") (pin "A1B12") (pinfunction "GND_A1B12_A1B12") (pintype "passive"))
      (node (ref "J4") (pin "B1A12") (pinfunction "GND_B1A12_B1A12") (pintype "passive"))
      (node (ref "J4") (pin "S1") (pinfunction "SHIELD_1_S1") (pintype "passive"))
      (node (ref "J4") (pin "S2") (pinfunction "SHIELD_2_S2") (pintype "passive"))
      (node (ref "J4") (pin "S3") (pinfunction "SHIELD_3_S3") (pintype "passive"))
      (node (ref "J4") (pin "S4") (pinfunction "SHIELD_4_S4") (pintype "passive"))
      (node (ref "R10") (pin "1") (pinfunction "1_1") (pintype "passive"))
      (node (ref "R11") (pin "1") (pinfunction "1_1") (pintype "passive"))
      (node (ref "R13") (pin "1") (pinfunction "1_1") (pintype "passive"))
      (node (ref "R14") (pin "1") (pinfunction "1_1") (pintype "passive"))
      (node (ref "R7") (pin "1") (pinfunction "1_1") (pintype "passive"))
      (node (ref "R9") (pin "1") (pinfunction "1_1") (pintype "passive"))
      (node (ref "SW1") (pin "3") (pinfunction "3_3") (pintype "passive"))
      (node (ref "SW1") (pin "4") (pinfunction "4_4") (pintype "passive"))
      (node (ref "SW2") (pin "3") (pinfunction "3_3") (pintype "passive"))
      (node (ref "SW2") (pin "4") (pinfunction "4_4") (pintype "passive"))
      (node (ref "U1") (pin "1") (pinfunction "GND_01_1") (pintype "passive"))
      (node (ref "U1") (pin "2") (pinfunction "GND_02_2") (pintype "passive"))
      (node (ref "U1") (pin "42") (pinfunction "GND_42") (pintype "passive"))
      (node (ref "U1") (pin "43") (pinfunction "GND_43") (pintype "passive"))
      (node (ref "U1") (pin "46") (pinfunction "GND_46_46") (pintype "passive"))
      (node (ref "U1") (pin "47") (pinfunction "GND_47_47") (pintype "passive"))
      (node (ref "U1") (pin "48") (pinfunction "GND_48_48") (pintype "passive"))
      (node (ref "U1") (pin "49") (pinfunction "GND_49_49") (pintype "passive"))
      (node (ref "U1") (pin "50") (pinfunction "GND_50_50") (pintype "passive"))
      (node (ref "U1") (pin "51") (pinfunction "GND_51_51") (pintype "passive"))
      (node (ref "U1") (pin "52") (pinfunction "GND_52_52") (pintype "passive"))
      (node (ref "U1") (pin "53") (pinfunction "GND_53_53") (pintype "passive"))
      (node (ref "U1") (pin "54") (pinfunction "GND_54_54") (pintype "passive"))
      (node (ref "U1") (pin "55") (pinfunction "GND_55_55") (pintype "passive"))
      (node (ref "U1") (pin "56") (pinfunction "GND_56_56") (pintype "passive"))
      (node (ref "U1") (pin "57") (pinfunction "GND_57_57") (pintype "passive"))
      (node (ref "U1") (pin "58") (pinfunction "GND_58_58") (pintype "passive"))
      (node (ref "U1") (pin "59") (pinfunction "GND_59_59") (pintype "passive"))
      (node (ref "U1") (pin "60") (pinfunction "GND_60_60") (pintype "passive"))
      (node (ref "U1") (pin "61") (pinfunction "GND_61_61") (pintype "passive"))
      (node (ref "U1") (pin "62") (pinfunction "GND_62_62") (pintype "passive"))
      (node (ref "U1") (pin "63") (pinfunction "GND_63_63") (pintype "passive"))
      (node (ref "U1") (pin "64") (pinfunction "GND_64_64") (pintype "passive"))
      (node (ref "U1") (pin "65") (pinfunction "GND_65_65") (pintype "passive"))
      (node (ref "U1") (pin "66") (pinfunction "GND_66_66") (pintype "passive"))
      (node (ref "U1") (pin "67") (pinfunction "GND_67_67") (pintype "passive"))
      (node (ref "U1") (pin "68") (pinfunction "GND_68_68") (pintype "passive"))
      (node (ref "U1") (pin "69") (pinfunction "GND_69_69") (pintype "passive"))
      (node (ref "U1") (pin "70") (pinfunction "GND_70_70") (pintype "passive"))
      (node (ref "U1") (pin "71") (pinfunction "GND_71_71") (pintype "passive"))
      (node (ref "U1") (pin "72") (pinfunction "GND_72_72") (pintype "passive"))
      (node (ref "U1") (pin "73") (pinfunction "GND_73_73") (pintype "passive"))
      (node (ref "U2") (pin "13") (pinfunction "GND_13") (pintype "passive"))
      (node (ref "U2") (pin "21") (pinfunction "GND_21") (pintype "passive"))
      (node (ref "U2") (pin "3") (pinfunction "GND_3") (pintype "passive"))
      (node (ref "U3") (pin "2") (pinfunction "GND_2") (pintype "power_in"))
      (node (ref "U3") (pin "4") (pinfunction "GND_4") (pintype "power_in"))
    )
    (net (code "65") (name "Net-(D4-Pad2)") (class "Default")
      (node (ref "D4") (pin "2") (pinfunction "2_2") (pintype "passive"))
      (node (ref "R12") (pin "1") (pinfunction "1_1") (pintype "passive"))
    )
    (net (code "66") (name "Net-(D8-Pad2)") (class "Default")
      (node (ref "D8") (pin "2") (pinfunction "2_2") (pintype "passive"))
      (node (ref "R15") (pin "1") (pinfunction "1_1") (pintype "passive"))
    )
    (net (code "67") (name "Net-(J3-CC1)") (class "Default")
      (node (ref "J3") (pin "A5") (pinfunction "CC1_A5") (pintype "passive"))
      (node (ref "R10") (pin "2") (pinfunction "2_2") (pintype "passive"))
    )
    (net (code "68") (name "Net-(J3-CC2)") (class "Default")
      (node (ref "J3") (pin "B5") (pinfunction "CC2_B5") (pintype "passive"))
      (node (ref "R9") (pin "2") (pinfunction "2_2") (pintype "passive"))
    )
    (net (code "69") (name "Net-(J4-CC1)") (class "Default")
      (node (ref "J4") (pin "A5") (pinfunction "CC1_A5") (pintype "passive"))
      (node (ref "R14") (pin "2") (pinfunction "2_2") (pintype "passive"))
    )
    (net (code "70") (name "Net-(J4-CC2)") (class "Default")
      (node (ref "J4") (pin "B5") (pinfunction "CC2_B5") (pintype "passive"))
      (node (ref "R13") (pin "2") (pinfunction "2_2") (pintype "passive"))
    )
    (net (code "71") (name "Net-(Q1-B)") (class "Default")
      (node (ref "Q1") (pin "1") (pinfunction "B_1") (pintype "passive"))
      (node (ref "R16") (pin "1") (pinfunction "1_1") (pintype "passive"))
    )
    (net (code "72") (name "Net-(Q2-B)") (class "Default")
      (node (ref "Q2") (pin "1") (pinfunction "B_1") (pintype "passive"))
      (node (ref "R18") (pin "1") (pinfunction "1_1") (pintype "passive"))
    )
    (net (code "73") (name "Net-(U2-CBUS0)") (class "Default")
      (node (ref "R7") (pin "2") (pinfunction "2_2") (pintype "passive"))
      (node (ref "U2") (pin "15") (pinfunction "CBUS0_15") (pintype "passive"))
    )
    (net (code "74") (name "unconnected-(J1-Pad24)") (class "Default")
      (node (ref "J1") (pin "24") (pinfunction "24_24") (pintype "passive+no_connect"))
    )
    (net (code "75") (name "unconnected-(J3-SBU1-PadA8)") (class "Default")
      (node (ref "J3") (pin "A8") (pinfunction "SBU1_A8") (pintype "passive+no_connect"))
    )
    (net (code "76") (name "unconnected-(J3-SBU2-PadB8)") (class "Default")
      (node (ref "J3") (pin "B8") (pinfunction "SBU2_B8") (pintype "passive+no_connect"))
    )
    (net (code "77") (name "unconnected-(J4-SBU1-PadA8)") (class "Default")
      (node (ref "J4") (pin "A8") (pinfunction "SBU1_A8") (pintype "passive+no_connect"))
    )
    (net (code "78") (name "unconnected-(J4-SBU2-PadB8)") (class "Default")
      (node (ref "J4") (pin "B8") (pinfunction "SBU2_B8") (pintype "passive+no_connect"))
    )
    (net (code "79") (name "unconnected-(U2-CBUS1-Pad14)") (class "Default")
      (node (ref "U2") (pin "14") (pinfunction "CBUS1_14") (pintype "passive+no_connect"))
    )
    (net (code "80") (name "unconnected-(U2-CBUS2-Pad7)") (class "Default")
      (node (ref "U2") (pin "7") (pinfunction "CBUS2_7") (pintype "passive+no_connect"))
    )
    (net (code "81") (name "unconnected-(U2-~{CTS}-Pad6)") (class "Default")
      (node (ref "U2") (pin "6") (pinfunction "~{CTS}_6") (pintype "passive+no_connect"))
    )
    (net (code "82") (name "unconnected-(U2-~{DCD}-Pad5)") (class "Default")
      (node (ref "U2") (pin "5") (pinfunction "~{DCD}_5") (pintype "passive+no_connect"))
    )
    (net (code "83") (name "unconnected-(U2-~{DSR}-Pad4)") (class "Default")
      (node (ref "U2") (pin "4") (pinfunction "~{DSR}_4") (pintype "passive+no_connect"))
    )
    (net (code "84") (name "unconnected-(U2-~{RI}-Pad2)") (class "Default")
      (node (ref "U2") (pin "2") (pinfunction "~{RI}_2") (pintype "passive+no_connect"))
    )
  )
)
